# SoundBoard.net
KiCad netlist of a schematic drawn in EAGLE
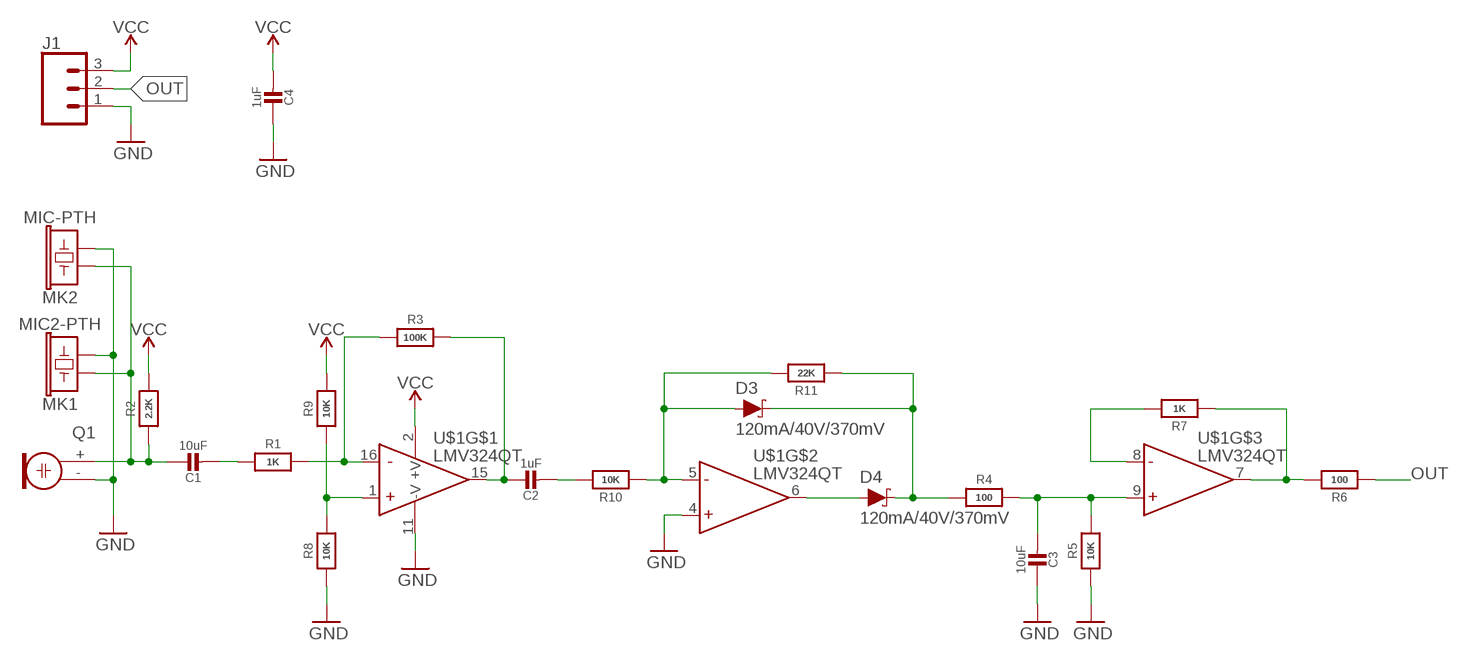
[diagram p0: schematic, sheet 1]

(export (version "E")
  (design (tool "Eeschema 10.0.6"))
  (components
    (comp (ref "C1")
      (value "10uF")
      (footprint "eagle-import:MICROBUILDER__0402MP")
      (libsource (lib "eagle-import") (part "MICROBUILDER_CAP_CERAMIC_0402MP"))
    )
    (comp (ref "C2")
      (value "1uF")
      (footprint "eagle-import:MICROBUILDER__0402MP")
      (libsource (lib "eagle-import") (part "MICROBUILDER_CAP_CERAMIC_0402MP"))
    )
    (comp (ref "C3")
      (value "10uF")
      (footprint "eagle-import:MICROBUILDER__0402MP")
      (libsource (lib "eagle-import") (part "MICROBUILDER_CAP_CERAMIC_0402MP"))
    )
    (comp (ref "C4")
      (value "1uF")
      (footprint "eagle-import:MICROBUILDER__0402MP")
      (libsource (lib "eagle-import") (part "MICROBUILDER_CAP_CERAMIC_0402MP"))
    )
    (comp (ref "D3")
      (value "120mA/40V/370mV")
      (footprint "eagle-import:SOD-523")
      (libsource (lib "eagle-import") (part "DIODE-SCHOTTKY-RB751S40"))
    )
    (comp (ref "D4")
      (value "120mA/40V/370mV")
      (footprint "eagle-import:SOD-523")
      (libsource (lib "eagle-import") (part "DIODE-SCHOTTKY-RB751S40"))
    )
    (comp (ref "J1")
      (value "CONN_03")
      (footprint "eagle-import:1X03")
      (libsource (lib "eagle-import") (part "CONN_03"))
    )
    (comp (ref "MK1")
      (value "MIC2-PTH")
      (footprint "eagle-import:MICROPHONE-PTH-4.0MM")
      (libsource (lib "eagle-import") (part "MIC2-PTH"))
    )
    (comp (ref "MK2")
      (value "MIC-PTH")
      (footprint "eagle-import:MICROPHONE-PTH-4.0MM")
      (libsource (lib "eagle-import") (part "MIC-PTH"))
    )
    (comp (ref "Q1")
      (value "ELECTRET")
      (footprint "eagle-import:9.7ELECTRET")
      (libsource (lib "eagle-import") (part "ELECTRET"))
    )
    (comp (ref "R1")
      (value "1K")
      (footprint "eagle-import:MICROBUILDER__0402MP")
      (libsource (lib "eagle-import") (part "MICROBUILDER_RESISTOR_0402MP"))
    )
    (comp (ref "R2")
      (value "2.2K")
      (footprint "eagle-import:MICROBUILDER__0402MP")
      (libsource (lib "eagle-import") (part "MICROBUILDER_RESISTOR_0402MP"))
    )
    (comp (ref "R3")
      (value "100K")
      (footprint "eagle-import:MICROBUILDER__0402MP")
      (libsource (lib "eagle-import") (part "MICROBUILDER_RESISTOR_0402MP"))
    )
    (comp (ref "R4")
      (value "100")
      (footprint "eagle-import:MICROBUILDER__0402MP")
      (libsource (lib "eagle-import") (part "MICROBUILDER_RESISTOR_0402MP"))
    )
    (comp (ref "R5")
      (value "10K")
      (footprint "eagle-import:MICROBUILDER__0402MP")
      (libsource (lib "eagle-import") (part "MICROBUILDER_RESISTOR_0402MP"))
    )
    (comp (ref "R6")
      (value "100")
      (footprint "eagle-import:MICROBUILDER__0402MP")
      (libsource (lib "eagle-import") (part "MICROBUILDER_RESISTOR_0402MP"))
    )
    (comp (ref "R7")
      (value "1K")
      (footprint "eagle-import:MICROBUILDER__0402MP")
      (libsource (lib "eagle-import") (part "MICROBUILDER_RESISTOR_0402MP"))
    )
    (comp (ref "R8")
      (value "10K")
      (footprint "eagle-import:MICROBUILDER__0402MP")
      (libsource (lib "eagle-import") (part "MICROBUILDER_RESISTOR_0402MP"))
    )
    (comp (ref "R9")
      (value "10K")
      (footprint "eagle-import:MICROBUILDER__0402MP")
      (libsource (lib "eagle-import") (part "MICROBUILDER_RESISTOR_0402MP"))
    )
    (comp (ref "R10")
      (value "10K")
      (footprint "eagle-import:MICROBUILDER__0402MP")
      (libsource (lib "eagle-import") (part "MICROBUILDER_RESISTOR_0402MP"))
    )
    (comp (ref "R11")
      (value "22K")
      (footprint "eagle-import:MICROBUILDER__0402MP")
      (libsource (lib "eagle-import") (part "MICROBUILDER_RESISTOR_0402MP"))
    )
    (comp (ref "U$1")
      (value "LMV324QT")
      (footprint "eagle-import:QFN-16_3X3")
      (libsource (lib "eagle-import") (part "LMV324QT"))
    )
  )
  (nets
    (net (code "1") (name "GND") (class "Default")
      (node (ref "C3") (pin "1") (pinfunction "1_1") (pintype "passive"))
      (node (ref "C4") (pin "1") (pinfunction "1_1") (pintype "passive"))
      (node (ref "J1") (pin "1") (pinfunction "1_1") (pintype "passive"))
      (node (ref "MK1") (pin "GND") (pinfunction "2_GND") (pintype "passive"))
      (node (ref "MK2") (pin "GND") (pinfunction "2_GND") (pintype "passive"))
      (node (ref "Q1") (pin "-") (pinfunction "1_-") (pintype "passive"))
      (node (ref "R5") (pin "1") (pinfunction "1_1") (pintype "passive"))
      (node (ref "R8") (pin "1") (pinfunction "1_1") (pintype "passive"))
      (node (ref "U$1") (pin "11") (pinfunction "-V_11") (pintype "power_in"))
      (node (ref "U$1") (pin "4") (pinfunction "+IN_4") (pintype "input"))
    )
    (net (code "2") (name "Net-(C1-Pad2)") (class "Default")
      (node (ref "C1") (pin "2") (pinfunction "2_2") (pintype "passive"))
      (node (ref "R1") (pin "1") (pinfunction "1_1") (pintype "passive"))
    )
    (net (code "3") (name "Net-(C2-Pad2)") (class "Default")
      (node (ref "C2") (pin "2") (pinfunction "2_2") (pintype "passive"))
      (node (ref "R10") (pin "2") (pinfunction "2_2") (pintype "passive"))
    )
    (net (code "4") (name "Net-(D3-PadC)") (class "Default")
      (node (ref "D3") (pin "C") (pinfunction "C_C") (pintype "passive"))
      (node (ref "D4") (pin "C") (pinfunction "C_C") (pintype "passive"))
      (node (ref "R11") (pin "1") (pinfunction "1_1") (pintype "passive"))
      (node (ref "R4") (pin "1") (pinfunction "1_1") (pintype "passive"))
    )
    (net (code "5") (name "Net-(MK1-1)") (class "Default")
      (node (ref "C1") (pin "1") (pinfunction "1_1") (pintype "passive"))
      (node (ref "MK1") (pin "OUT") (pinfunction "1_OUT") (pintype "passive"))
      (node (ref "MK2") (pin "OUT") (pinfunction "1_OUT") (pintype "passive"))
      (node (ref "Q1") (pin "+") (pinfunction "2_+") (pintype "passive"))
      (node (ref "R2") (pin "1") (pinfunction "1_1") (pintype "passive"))
    )
    (net (code "6") (name "Net-(U$1A-+IN)") (class "Default")
      (node (ref "R8") (pin "2") (pinfunction "2_2") (pintype "passive"))
      (node (ref "R9") (pin "1") (pinfunction "1_1") (pintype "passive"))
      (node (ref "U$1") (pin "1") (pinfunction "+IN_1") (pintype "input"))
    )
    (net (code "7") (name "Net-(U$1A--IN)") (class "Default")
      (node (ref "R1") (pin "2") (pinfunction "2_2") (pintype "passive"))
      (node (ref "R3") (pin "1") (pinfunction "1_1") (pintype "passive"))
      (node (ref "U$1") (pin "16") (pinfunction "-IN_16") (pintype "input"))
    )
    (net (code "8") (name "Net-(U$1A-OUT)") (class "Default")
      (node (ref "C2") (pin "1") (pinfunction "1_1") (pintype "passive"))
      (node (ref "R3") (pin "2") (pinfunction "2_2") (pintype "passive"))
      (node (ref "U$1") (pin "15") (pinfunction "OUT_15") (pintype "output"))
    )
    (net (code "9") (name "Net-(U$1B--IN)") (class "Default")
      (node (ref "D3") (pin "A") (pinfunction "A_A") (pintype "passive"))
      (node (ref "R10") (pin "1") (pinfunction "1_1") (pintype "passive"))
      (node (ref "R11") (pin "2") (pinfunction "2_2") (pintype "passive"))
      (node (ref "U$1") (pin "5") (pinfunction "-IN_5") (pintype "input"))
    )
    (net (code "10") (name "Net-(U$1B-OUT)") (class "Default")
      (node (ref "D4") (pin "A") (pinfunction "A_A") (pintype "passive"))
      (node (ref "U$1") (pin "6") (pinfunction "OUT_6") (pintype "output"))
    )
    (net (code "11") (name "Net-(U$1C-+IN)") (class "Default")
      (node (ref "C3") (pin "2") (pinfunction "2_2") (pintype "passive"))
      (node (ref "R4") (pin "2") (pinfunction "2_2") (pintype "passive"))
      (node (ref "R5") (pin "2") (pinfunction "2_2") (pintype "passive"))
      (node (ref "U$1") (pin "9") (pinfunction "+IN_9") (pintype "input"))
    )
    (net (code "12") (name "Net-(U$1C--IN)") (class "Default")
      (node (ref "R7") (pin "2") (pinfunction "2_2") (pintype "passive"))
      (node (ref "U$1") (pin "8") (pinfunction "-IN_8") (pintype "input"))
    )
    (net (code "13") (name "Net-(U$1C-OUT)") (class "Default")
      (node (ref "R6") (pin "2") (pinfunction "2_2") (pintype "passive"))
      (node (ref "R7") (pin "1") (pinfunction "1_1") (pintype "passive"))
      (node (ref "U$1") (pin "7") (pinfunction "OUT_7") (pintype "output"))
    )
    (net (code "14") (name "OUT") (class "Default")
      (node (ref "J1") (pin "2") (pinfunction "2_2") (pintype "passive"))
      (node (ref "R6") (pin "1") (pinfunction "1_1") (pintype "passive"))
    )
    (net (code "15") (name "VCC") (class "Default")
      (node (ref "C4") (pin "2") (pinfunction "2_2") (pintype "passive"))
      (node (ref "J1") (pin "3") (pinfunction "3_3") (pintype "passive"))
      (node (ref "R2") (pin "2") (pinfunction "2_2") (pintype "passive"))
      (node (ref "R9") (pin "2") (pinfunction "2_2") (pintype "passive"))
      (node (ref "U$1") (pin "2") (pinfunction "+V_2") (pintype "power_in"))
    )
  )
)
